# asynchronous.net
KiCad netlist of a schematic drawn in Altium Designer
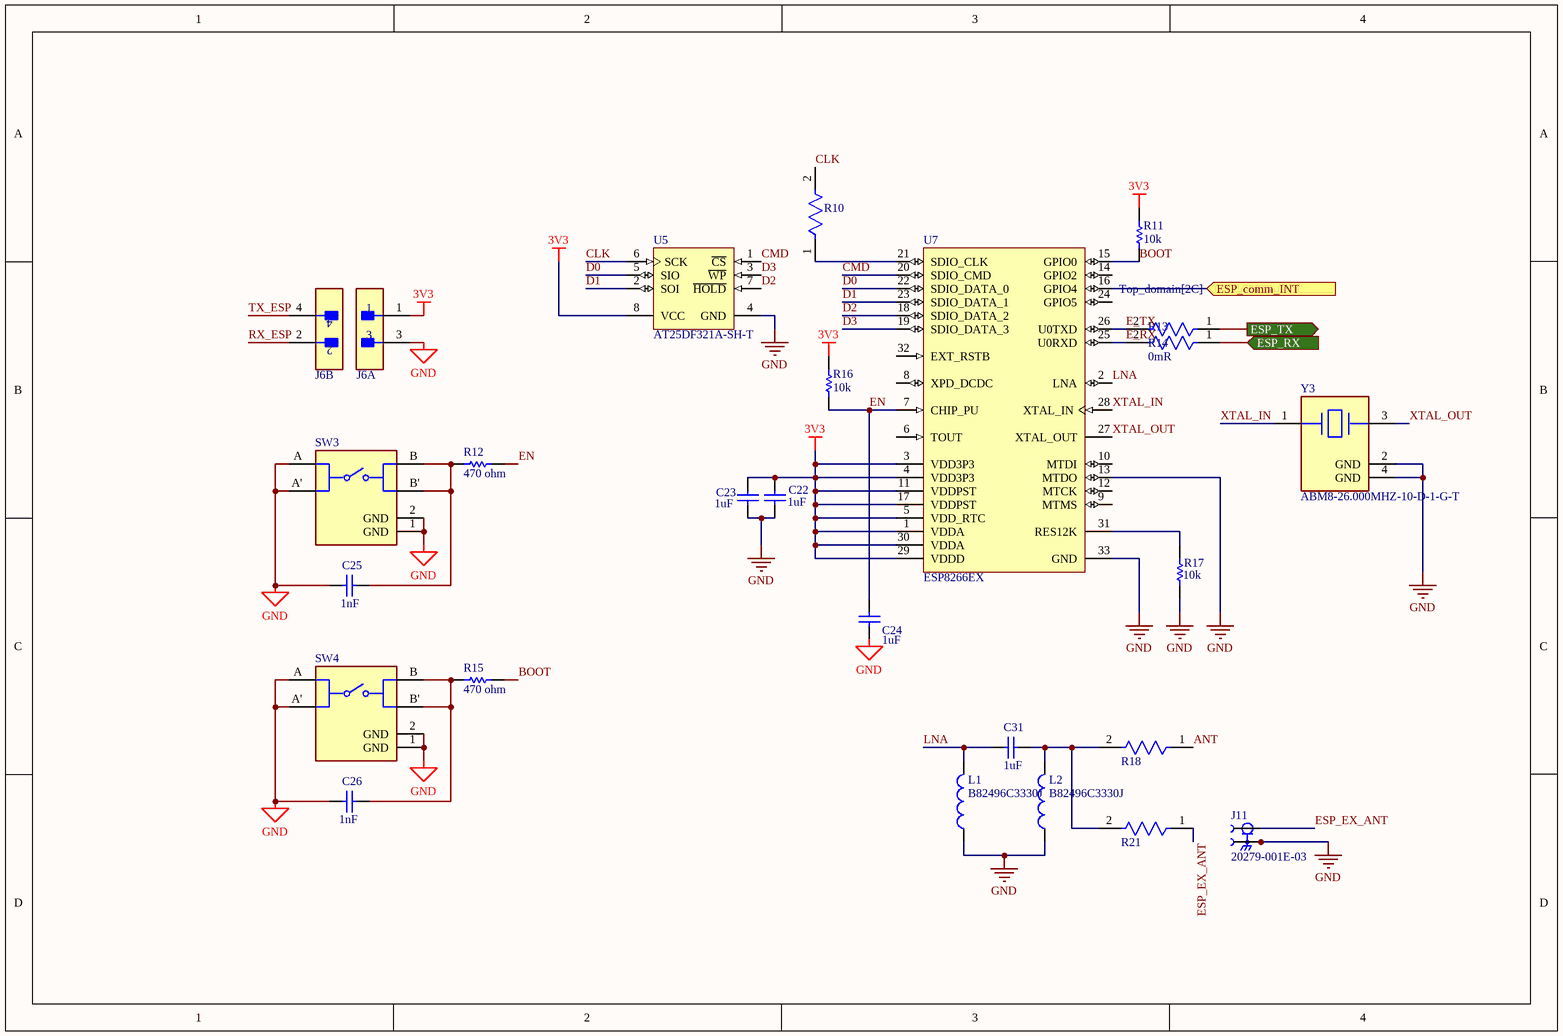
[diagram p0: asynchronous.SchDoc]

(export (version "E")
  (design (tool "Eeschema 10.0.6"))
  (components
    (comp (ref "C22")
      (value "C0805C105K4PACTU")
      (footprint "CAPC2013X145X50LL20T25")
      (fields (field (name "MANUFACTURER") "Kemet") (field (name "PARAMETER 1") "1uF"))
      (libsource (lib "Altium Content Vault") (part "CAP"))
    )
    (comp (ref "C23")
      (value "C0805C105K4PACTU")
      (footprint "CAPC2013X145X50LL20T25")
      (fields (field (name "MANUFACTURER") "Kemet") (field (name "PARAMETER 1") "1uF"))
      (libsource (lib "Altium Content Vault") (part "CAP"))
    )
    (comp (ref "C24")
      (value "C0805C105K4PACTU")
      (footprint "CAPC2013X145X50LL20T25")
      (fields (field (name "MANUFACTURER") "Kemet") (field (name "PARAMETER 1") "1uF"))
      (libsource (lib "Altium Content Vault") (part "CAP"))
    )
    (comp (ref "C25")
      (value "VJ0805D102KXAAJ")
      (footprint "CAPC2013X145X48LL20T23")
      (fields (field (name "MANUFACTURER") "Vitramon") (field (name "PARAMETER 1") "1nF"))
      (libsource (lib "Altium Content Vault") (part "CAP"))
    )
    (comp (ref "C26")
      (value "VJ0805D102KXAAJ")
      (footprint "CAPC2013X145X48LL20T23")
      (fields (field (name "MANUFACTURER") "Vitramon") (field (name "PARAMETER 1") "1nF"))
      (libsource (lib "Altium Content Vault") (part "CAP"))
    )
    (comp (ref "C31")
      (value "C0805C105K4PACTU")
      (footprint "CAPC2013X145X50LL20T25")
      (fields (field (name "MANUFACTURER") "Kemet") (field (name "PARAMETER 1") "1uF"))
      (libsource (lib "Altium Content Vault") (part "CAP"))
    )
    (comp (ref "J6")
      (value "PEC02DABN")
      (footprint "FP-PEC02DABN-MFG")
      (description "CONN HEADER VERT 4POS 2.54MM")
      (libsource (lib "") (part "1621473add15499e993d6bbd36d0f06_1"))
    )
    (comp (ref "J11")
      (value "20279-001E-03")
      (footprint "IPEX_20279-001E-03")
      (fields (field (name "MF") "I-PEX"))
      (libsource (lib "20279-001E-03") (part "20279-001E-03"))
    )
    (comp (ref "L1")
      (value "B82496C3330J")
      (footprint "INDC1608X90X30LL10T20")
      (fields (field (name "MANUFACTURER") "EPCOS-(TDK)") (field (name "TOLERANCE") "±5%"))
      (libsource (lib "Altium Content Vault") (part "IND-2"))
    )
    (comp (ref "L2")
      (value "B82496C3330J")
      (footprint "INDC1608X90X30LL10T20")
      (fields (field (name "MANUFACTURER") "EPCOS-(TDK)") (field (name "TOLERANCE") "±5%"))
      (libsource (lib "Altium Content Vault") (part "IND-2"))
    )
    (comp (ref "R10")
      (value "CR0805-J/-000ELF")
      (footprint "FP-CR0805-IPC_C")
      (description "Thick Film Chip Resistors 0805 0Ω 0.125W 5%")
      (fields (field (name "TOLERANCE") "5%"))
      (libsource (lib "Altium Content Vault") (part "1029c3af85768c4190bb7ad29bc67b5"))
    )
    (comp (ref "R11")
      (value "RC0805FR-0710KL")
      (footprint "RESC2013X60X35NL10T20")
      (description "Chip Resistor, 10 KOhm, +/- 1%, 0.125 W, -55 to 155 degC, 0805 (2012 Metric), RoHS, Tape and Reel")
      (fields (field (name "MANUFACTURER") "Yageo") (field (name "PARAMETER 1") "10k"))
      (libsource (lib "Altium Content Vault") (part "RES-2"))
    )
    (comp (ref "R12")
      (value "CRCW0805470RFKEA")
      (footprint "RESC2013X50X30LL20T20")
      (fields (field (name "MANUFACTURER") "Vishay Dale") (field (name "PARAMETER 1") "470 ohm"))
      (libsource (lib "Altium Content Vault") (part "RES"))
    )
    (comp (ref "R13")
      (value "CR0805-J/-000ELF")
      (footprint "FP-CR0805-IPC_C")
      (description "Thick Film Chip Resistors 0805 0Ω 0.125W 5%")
      (fields (field (name "RESISTANCE") "0mR") (field (name "TOLERANCE") "5%"))
      (libsource (lib "Altium Content Vault") (part "1029c3af85768c4190bb7ad29bc67b5"))
    )
    (comp (ref "R14")
      (value "CR0805-J/-000ELF")
      (footprint "FP-CR0805-IPC_C")
      (description "Thick Film Chip Resistors 0805 0Ω 0.125W 5%")
      (fields (field (name "TOLERANCE") "5%"))
      (libsource (lib "Altium Content Vault") (part "1029c3af85768c4190bb7ad29bc67b5"))
    )
    (comp (ref "R15")
      (value "CRCW0805470RFKEA")
      (footprint "RESC2013X50X30LL20T20")
      (fields (field (name "MANUFACTURER") "Vishay Dale") (field (name "PARAMETER 1") "470 ohm"))
      (libsource (lib "Altium Content Vault") (part "RES"))
    )
    (comp (ref "R16")
      (value "RC0805FR-0710KL")
      (footprint "RESC2013X60X35NL10T20")
      (description "Chip Resistor, 10 KOhm, +/- 1%, 0.125 W, -55 to 155 degC, 0805 (2012 Metric), RoHS, Tape and Reel")
      (fields (field (name "MANUFACTURER") "Yageo") (field (name "PARAMETER 1") "10k"))
      (libsource (lib "Altium Content Vault") (part "RES-2"))
    )
    (comp (ref "R17")
      (value "RC0805FR-0710KL")
      (footprint "RESC2013X60X35NL10T20")
      (description "Chip Resistor, 10 KOhm, +/- 1%, 0.125 W, -55 to 155 degC, 0805 (2012 Metric), RoHS, Tape and Reel")
      (fields (field (name "MANUFACTURER") "Yageo") (field (name "PARAMETER 1") "10k"))
      (libsource (lib "Altium Content Vault") (part "RES-2"))
    )
    (comp (ref "R18")
      (value "CR0805-J/-000ELF")
      (footprint "FP-CR0805-IPC_C")
      (description "Thick Film Chip Resistors 0805 0Ω 0.125W 5%")
      (fields (field (name "TOLERANCE") "5%"))
      (libsource (lib "Altium Content Vault") (part "1029c3af85768c4190bb7ad29bc67b5"))
    )
    (comp (ref "R21")
      (value "CR0805-J/-000ELF")
      (footprint "FP-CR0805-IPC_C")
      (description "Thick Film Chip Resistors 0805 0Ω 0.125W 5%")
      (fields (field (name "TOLERANCE") "5%"))
      (libsource (lib "Altium Content Vault") (part "1029c3af85768c4190bb7ad29bc67b5"))
    )
    (comp (ref "SW3")
      (value "EVQ-PLMA15")
      (footprint "FP-EVQ-PLMA15-MFG")
      (description "SWITCH TACTILE SPST-NO 0.02A 15V")
      (fields
        (field (name "OCTOPART") "https://octopart.com/evq-plma15-panasonic-39850235")
        (field (name "MANUFACTURER") "Panasonic Electronic Components")
      )
      (libsource (lib "Altium Content Vault") (part "fc7b47d2e4813f0909612a6c4f63938"))
    )
    (comp (ref "SW4")
      (value "EVQ-PLMA15")
      (footprint "FP-EVQ-PLMA15-MFG")
      (description "SWITCH TACTILE SPST-NO 0.02A 15V")
      (fields
        (field (name "OCTOPART") "https://octopart.com/evq-plma15-panasonic-39850235")
        (field (name "MANUFACTURER") "Panasonic Electronic Components")
      )
      (libsource (lib "Altium Content Vault") (part "fc7b47d2e4813f0909612a6c4f63938"))
    )
    (comp (ref "U5")
      (value "AT25DF321A-SH-T")
      (footprint "ADST-S2-8_N")
      (fields (field (name "MANUFACTURER") "Adesto"))
      (libsource (lib "Altium Content Vault") (part "ADST-AT25DF321A-8"))
    )
    (comp (ref "U7")
      (value "ESP8266EX")
      (footprint "ESFS-QFN-32_L")
      (description "Low-Power, Highly-Integrated Wi-Fi Solution, 2.5 to 3.6 V, 80 mA, -40 to 125 degC, 32-Pin QFN")
      (fields (field (name "MANUFACTURER") "Espressif Systems"))
      (libsource (lib "Altium Content Vault") (part "ESFS-ESP8266EX-32"))
    )
    (comp (ref "Y3")
      (value "ABM8-26.000MHZ-10-D-1-G-T")
      (footprint "FP-ABM8-MFG")
      (description "Crystal 26MHz ±10ppm 10pF SMD-4 3.2mm x 2.5mm")
      (libsource (lib "Altium Content Vault") (part "dfdb7f9a12507849fb681da9a70121c"))
    )
  )
  (nets
    (net (code "1") (name "/ANT") (class "Default")
      (node (ref "R18") (pin "1") (pinfunction "1_1") (pintype "passive"))
    )
    (net (code "2") (name "/BOOT") (class "Default")
      (node (ref "R11") (pin "2") (pinfunction "2_2") (pintype "passive"))
      (node (ref "R15") (pin "2") (pinfunction "2_2") (pintype "passive"))
      (node (ref "U7") (pin "15") (pinfunction "GPIO0_15") (pintype "bidirectional"))
    )
    (net (code "3") (name "/CLK") (class "Default")
      (node (ref "R10") (pin "2") (pinfunction "2_2") (pintype "passive"))
      (node (ref "U5") (pin "6") (pinfunction "SCK_6") (pintype "input"))
    )
    (net (code "4") (name "/CMD") (class "Default")
      (node (ref "U5") (pin "1") (pinfunction "~{CS}_1") (pintype "input"))
      (node (ref "U7") (pin "20") (pinfunction "SDIO_CMD_20") (pintype "bidirectional"))
    )
    (net (code "5") (name "/D0") (class "Default")
      (node (ref "U5") (pin "5") (pinfunction "SIO_5") (pintype "bidirectional"))
      (node (ref "U7") (pin "22") (pinfunction "SDIO_DATA_0_22") (pintype "bidirectional"))
    )
    (net (code "6") (name "/D1") (class "Default")
      (node (ref "U5") (pin "2") (pinfunction "SOI_2") (pintype "bidirectional"))
      (node (ref "U7") (pin "23") (pinfunction "SDIO_DATA_1_23") (pintype "bidirectional"))
    )
    (net (code "7") (name "/D2") (class "Default")
      (node (ref "U5") (pin "7") (pinfunction "~{HOLD}_7") (pintype "input"))
      (node (ref "U7") (pin "18") (pinfunction "SDIO_DATA_2_18") (pintype "bidirectional"))
    )
    (net (code "8") (name "/D3") (class "Default")
      (node (ref "U5") (pin "3") (pinfunction "~{WP}_3") (pintype "input"))
      (node (ref "U7") (pin "19") (pinfunction "SDIO_DATA_3_19") (pintype "bidirectional"))
    )
    (net (code "9") (name "/EN") (class "Default")
      (node (ref "C24") (pin "2") (pinfunction "2_2") (pintype "passive"))
      (node (ref "R12") (pin "2") (pinfunction "2_2") (pintype "passive"))
      (node (ref "R16") (pin "2") (pinfunction "2_2") (pintype "passive"))
      (node (ref "U7") (pin "7") (pinfunction "CHIP_PU_7") (pintype "input"))
    )
    (net (code "10") (name "/ESP_EX_ANT") (class "Default")
      (node (ref "J11") (pin "1") (pinfunction "SIGNAL_1") (pintype "passive"))
      (node (ref "R21") (pin "1") (pinfunction "1_1") (pintype "passive"))
    )
    (net (code "11") (name "/ESP_RX") (class "Default")
      (node (ref "R13") (pin "1") (pinfunction "1_1") (pintype "passive"))
    )
    (net (code "12") (name "/ESP_TX") (class "Default")
      (node (ref "R14") (pin "1") (pinfunction "1_1") (pintype "passive"))
    )
    (net (code "13") (name "/ESP_comm_INT") (class "Default")
      (node (ref "U7") (pin "16") (pinfunction "GPIO4_16") (pintype "bidirectional"))
    )
    (net (code "14") (name "/E_RX") (class "Default")
      (node (ref "R13") (pin "2") (pinfunction "2_2") (pintype "passive"))
      (node (ref "U7") (pin "25") (pinfunction "U0RXD_25") (pintype "bidirectional"))
    )
    (net (code "15") (name "/E_TX") (class "Default")
      (node (ref "R14") (pin "2") (pinfunction "2_2") (pintype "passive"))
      (node (ref "U7") (pin "26") (pinfunction "U0TXD_26") (pintype "bidirectional"))
    )
    (net (code "16") (name "/LNA") (class "Default")
      (node (ref "C31") (pin "2") (pinfunction "2_2") (pintype "passive"))
      (node (ref "L1") (pin "2") (pinfunction "2_2") (pintype "passive"))
      (node (ref "U7") (pin "2") (pinfunction "LNA_2") (pintype "bidirectional"))
    )
    (net (code "17") (name "/RX_ESP") (class "Default")
      (node (ref "J6") (pin "2") (pinfunction "2_2") (pintype "passive"))
    )
    (net (code "18") (name "/TX_ESP") (class "Default")
      (node (ref "J6") (pin "4") (pinfunction "4_4") (pintype "passive"))
    )
    (net (code "19") (name "/XTAL_IN") (class "Default")
      (node (ref "U7") (pin "28") (pinfunction "XTAL_IN_28") (pintype "input"))
      (node (ref "Y3") (pin "1") (pinfunction "1_1") (pintype "passive"))
    )
    (net (code "20") (name "/XTAL_OUT") (class "Default")
      (node (ref "U7") (pin "27") (pinfunction "XTAL_OUT_27") (pintype "passive"))
      (node (ref "Y3") (pin "3") (pinfunction "3_3") (pintype "passive"))
    )
    (net (code "21") (name "3V3") (class "Default")
      (node (ref "C22") (pin "2") (pinfunction "2_2") (pintype "passive"))
      (node (ref "C23") (pin "2") (pinfunction "2_2") (pintype "passive"))
      (node (ref "J6") (pin "1") (pinfunction "1_1") (pintype "passive"))
      (node (ref "R11") (pin "1") (pinfunction "1_1") (pintype "passive"))
      (node (ref "R16") (pin "1") (pinfunction "1_1") (pintype "passive"))
      (node (ref "U5") (pin "8") (pinfunction "VCC_8") (pintype "power_in"))
      (node (ref "U7") (pin "1") (pinfunction "VDDA_1") (pintype "power_in"))
      (node (ref "U7") (pin "11") (pinfunction "VDDPST_11") (pintype "power_in"))
      (node (ref "U7") (pin "17") (pinfunction "VDDPST_17") (pintype "power_in"))
      (node (ref "U7") (pin "29") (pinfunction "VDDD_29") (pintype "power_in"))
      (node (ref "U7") (pin "3") (pinfunction "VDD3P3_3") (pintype "power_in"))
      (node (ref "U7") (pin "30") (pinfunction "VDDA_30") (pintype "power_in"))
      (node (ref "U7") (pin "4") (pinfunction "VDD3P3_4") (pintype "power_in"))
      (node (ref "U7") (pin "5") (pinfunction "VDD_RTC_5") (pintype "power_in"))
    )
    (net (code "22") (name "GND") (class "Default")
      (node (ref "C22") (pin "1") (pinfunction "1_1") (pintype "passive"))
      (node (ref "C23") (pin "1") (pinfunction "1_1") (pintype "passive"))
      (node (ref "C24") (pin "1") (pinfunction "1_1") (pintype "passive"))
      (node (ref "C25") (pin "1") (pinfunction "1_1") (pintype "passive"))
      (node (ref "C26") (pin "1") (pinfunction "1_1") (pintype "passive"))
      (node (ref "J11") (pin "2") (pinfunction "GROUND_2") (pintype "passive"))
      (node (ref "J11") (pin "3") (pinfunction "GROUND_3") (pintype "passive"))
      (node (ref "J6") (pin "3") (pinfunction "3_3") (pintype "passive"))
      (node (ref "L1") (pin "1") (pinfunction "1_1") (pintype "passive"))
      (node (ref "L2") (pin "1") (pinfunction "1_1") (pintype "passive"))
      (node (ref "R17") (pin "1") (pinfunction "1_1") (pintype "passive"))
      (node (ref "SW3") (pin "1") (pinfunction "GND_1") (pintype "power_in"))
      (node (ref "SW3") (pin "2") (pinfunction "GND_2") (pintype "power_in"))
      (node (ref "SW3") (pin "A") (pinfunction "A_A") (pintype "passive"))
      (node (ref "SW3") (pin "A'") (pinfunction "A'_A'") (pintype "passive"))
      (node (ref "SW4") (pin "1") (pinfunction "GND_1") (pintype "power_in"))
      (node (ref "SW4") (pin "2") (pinfunction "GND_2") (pintype "power_in"))
      (node (ref "SW4") (pin "A") (pinfunction "A_A") (pintype "passive"))
      (node (ref "SW4") (pin "A'") (pinfunction "A'_A'") (pintype "passive"))
      (node (ref "U5") (pin "4") (pinfunction "GND_4") (pintype "power_in"))
      (node (ref "U7") (pin "13") (pinfunction "MTDO_13") (pintype "bidirectional"))
      (node (ref "U7") (pin "33") (pinfunction "GND_33") (pintype "power_in"))
      (node (ref "Y3") (pin "2") (pinfunction "GND_2") (pintype "power_in"))
      (node (ref "Y3") (pin "4") (pinfunction "GND_4") (pintype "power_in"))
    )
    (net (code "23") (name "Net-(C25-Pad2)") (class "Default")
      (node (ref "C25") (pin "2") (pinfunction "2_2") (pintype "passive"))
      (node (ref "R12") (pin "1") (pinfunction "1_1") (pintype "passive"))
      (node (ref "SW3") (pin "B") (pinfunction "B_B") (pintype "passive"))
      (node (ref "SW3") (pin "B'") (pinfunction "B'_B'") (pintype "passive"))
    )
    (net (code "24") (name "Net-(C26-Pad2)") (class "Default")
      (node (ref "C26") (pin "2") (pinfunction "2_2") (pintype "passive"))
      (node (ref "R15") (pin "1") (pinfunction "1_1") (pintype "passive"))
      (node (ref "SW4") (pin "B") (pinfunction "B_B") (pintype "passive"))
      (node (ref "SW4") (pin "B'") (pinfunction "B'_B'") (pintype "passive"))
    )
    (net (code "25") (name "Net-(C31-Pad1)") (class "Default")
      (node (ref "C31") (pin "1") (pinfunction "1_1") (pintype "passive"))
      (node (ref "L2") (pin "2") (pinfunction "2_2") (pintype "passive"))
      (node (ref "R18") (pin "2") (pinfunction "2_2") (pintype "passive"))
      (node (ref "R21") (pin "2") (pinfunction "2_2") (pintype "passive"))
    )
    (net (code "26") (name "Net-(U7-RES12K)") (class "Default")
      (node (ref "R17") (pin "2") (pinfunction "2_2") (pintype "passive"))
      (node (ref "U7") (pin "31") (pinfunction "RES12K_31") (pintype "passive"))
    )
    (net (code "27") (name "Net-(U7-SDIO_CLK)") (class "Default")
      (node (ref "R10") (pin "1") (pinfunction "1_1") (pintype "passive"))
      (node (ref "U7") (pin "21") (pinfunction "SDIO_CLK_21") (pintype "bidirectional"))
    )
    (net (code "28") (name "unconnected-(U7-EXT_RSTB-Pad32)") (class "Default")
      (node (ref "U7") (pin "32") (pinfunction "EXT_RSTB_32") (pintype "input"))
    )
    (net (code "29") (name "unconnected-(U7-GPIO2-Pad14)") (class "Default")
      (node (ref "U7") (pin "14") (pinfunction "GPIO2_14") (pintype "bidirectional"))
    )
    (net (code "30") (name "unconnected-(U7-GPIO5-Pad24)") (class "Default")
      (node (ref "U7") (pin "24") (pinfunction "GPIO5_24") (pintype "bidirectional"))
    )
    (net (code "31") (name "unconnected-(U7-MTCK-Pad12)") (class "Default")
      (node (ref "U7") (pin "12") (pinfunction "MTCK_12") (pintype "bidirectional"))
    )
    (net (code "32") (name "unconnected-(U7-MTDI-Pad10)") (class "Default")
      (node (ref "U7") (pin "10") (pinfunction "MTDI_10") (pintype "bidirectional"))
    )
    (net (code "33") (name "unconnected-(U7-MTMS-Pad9)") (class "Default")
      (node (ref "U7") (pin "9") (pinfunction "MTMS_9") (pintype "bidirectional"))
    )
    (net (code "34") (name "unconnected-(U7-TOUT-Pad6)") (class "Default")
      (node (ref "U7") (pin "6") (pinfunction "TOUT_6") (pintype "input"))
    )
    (net (code "35") (name "unconnected-(U7-XPD_DCDC-Pad8)") (class "Default")
      (node (ref "U7") (pin "8") (pinfunction "XPD_DCDC_8") (pintype "bidirectional"))
    )
  )
)
